# skv_v3.net
KiCad netlist of a schematic drawn in EAGLE
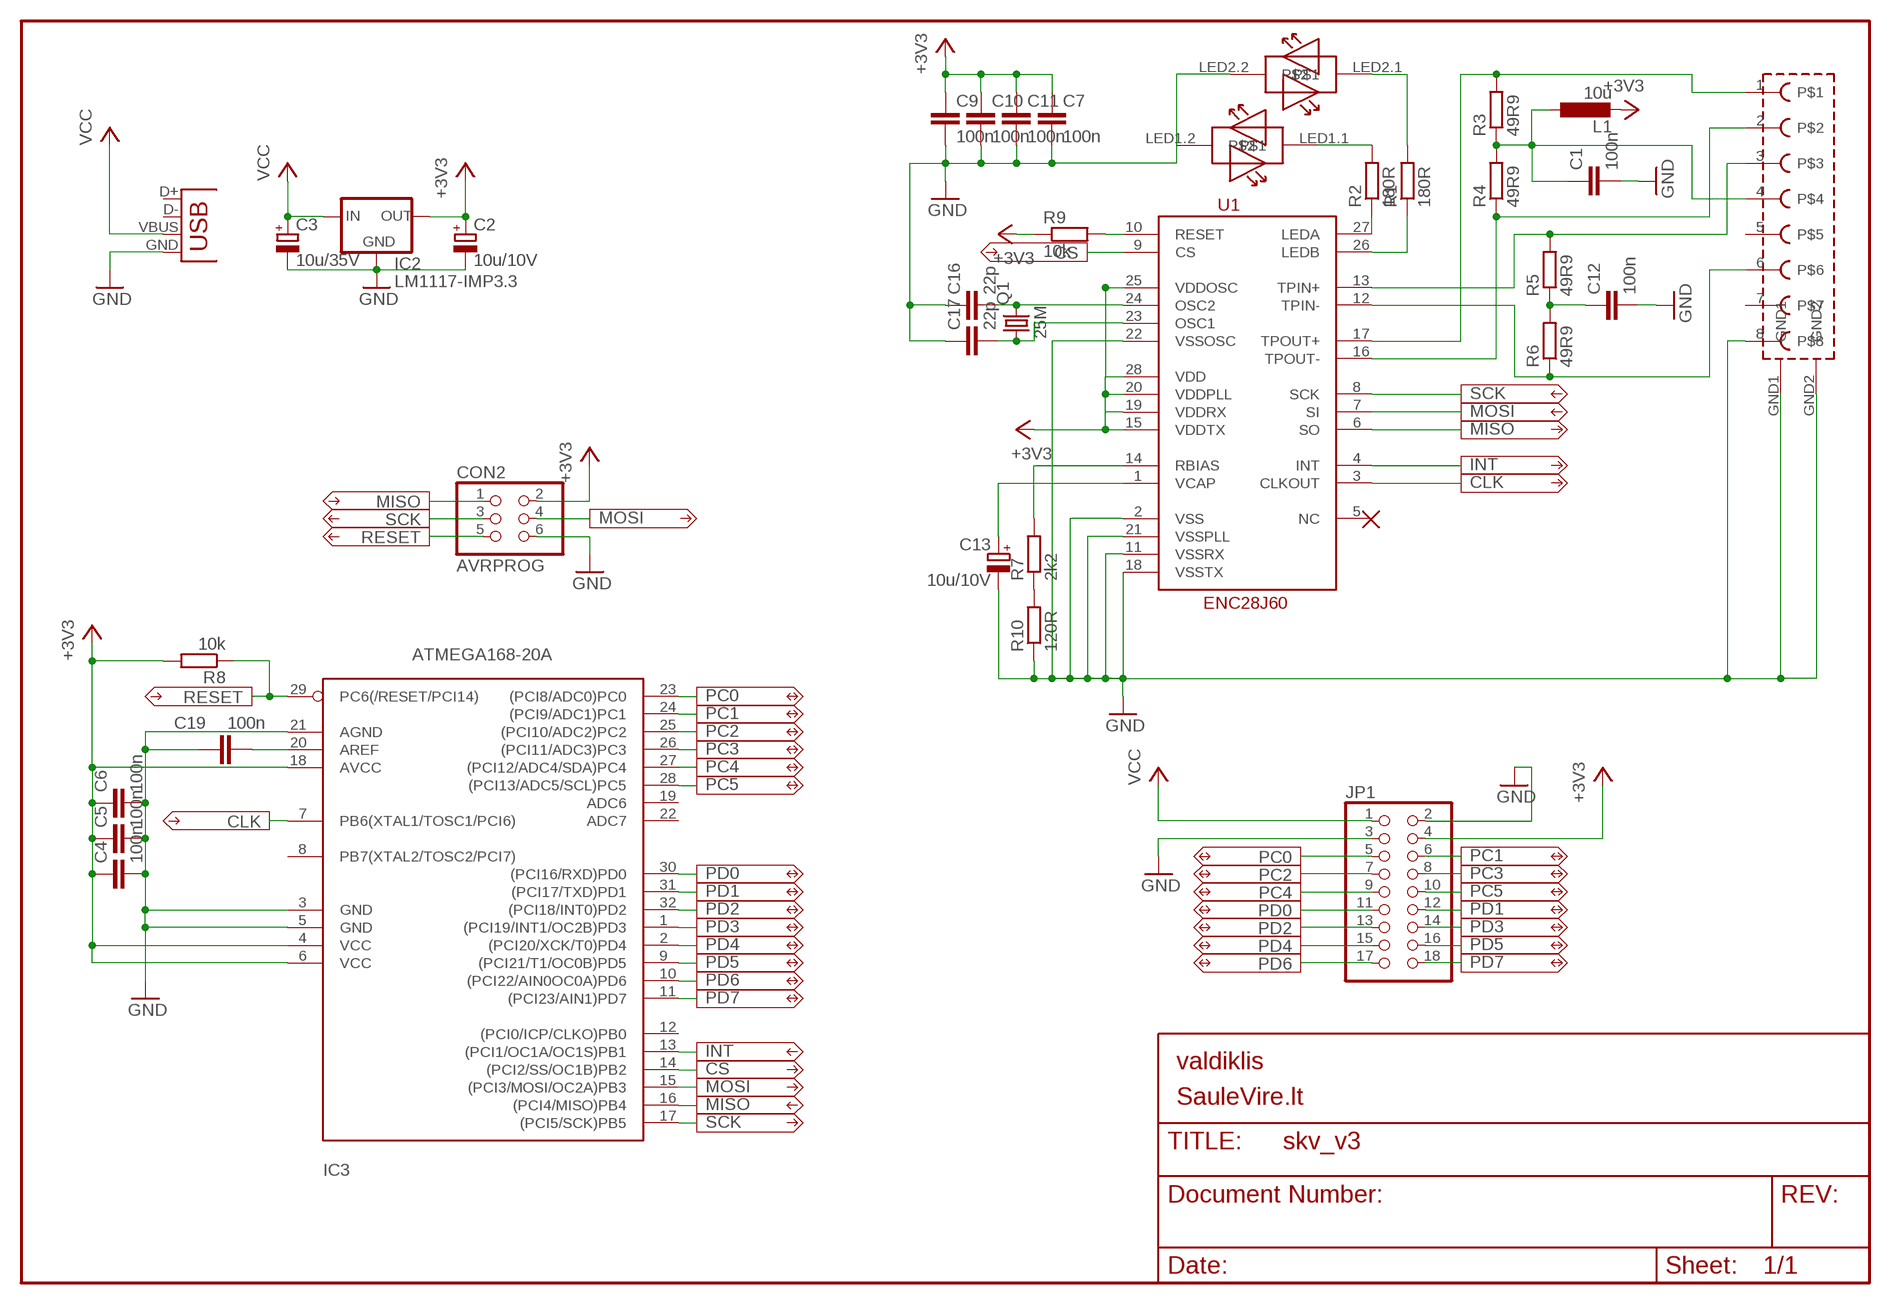
[diagram p0: schematic, sheet 1]

(export (version "E")
  (design (tool "Eeschema 10.0.6"))
  (components
    (comp (ref "C1")
      (value "100n")
      (footprint "eagle-import:C0805")
      (libsource (lib "eagle-import") (part "C-EUC0805"))
    )
    (comp (ref "C2")
      (value "10u/10V")
      (footprint "eagle-import:SMC_A")
      (libsource (lib "eagle-import") (part "CPOL-EUSMCA"))
    )
    (comp (ref "C3")
      (value "10u/35V")
      (footprint "eagle-import:SMC_C")
      (libsource (lib "eagle-import") (part "CPOL-EUSMCC"))
    )
    (comp (ref "C4")
      (value "100n")
      (footprint "eagle-import:C0805")
      (libsource (lib "eagle-import") (part "C-EUC0805"))
    )
    (comp (ref "C5")
      (value "100n")
      (footprint "eagle-import:C0805")
      (libsource (lib "eagle-import") (part "C-EUC0805"))
    )
    (comp (ref "C6")
      (value "100n")
      (footprint "eagle-import:C0805")
      (libsource (lib "eagle-import") (part "C-EUC0805"))
    )
    (comp (ref "C7")
      (value "100n")
      (footprint "eagle-import:C0805")
      (libsource (lib "eagle-import") (part "C-EUC0805"))
    )
    (comp (ref "C9")
      (value "100n")
      (footprint "eagle-import:C0805")
      (libsource (lib "eagle-import") (part "C-EUC0805"))
    )
    (comp (ref "C10")
      (value "100n")
      (footprint "eagle-import:C0805")
      (libsource (lib "eagle-import") (part "C-EUC0805"))
    )
    (comp (ref "C11")
      (value "100n")
      (footprint "eagle-import:C0805")
      (libsource (lib "eagle-import") (part "C-EUC0805"))
    )
    (comp (ref "C12")
      (value "100n")
      (footprint "eagle-import:C0805")
      (libsource (lib "eagle-import") (part "C-EUC0805"))
    )
    (comp (ref "C13")
      (value "10u/10V")
      (footprint "eagle-import:SMC_A")
      (libsource (lib "eagle-import") (part "CPOL-EUSMCA"))
    )
    (comp (ref "C16")
      (value "22p")
      (footprint "eagle-import:C0805")
      (libsource (lib "eagle-import") (part "C-EUC0805"))
    )
    (comp (ref "C17")
      (value "22p")
      (footprint "eagle-import:C0805")
      (libsource (lib "eagle-import") (part "C-EUC0805"))
    )
    (comp (ref "C19")
      (value "100n")
      (footprint "eagle-import:C0805")
      (libsource (lib "eagle-import") (part "C-EUC0805"))
    )
    (comp (ref "CON2")
      (value "AVRPROG")
      (footprint "eagle-import:2X03")
      (libsource (lib "eagle-import") (part "PINHD-2X3_2.54"))
    )
    (comp (ref "IC2")
      (value "LM1117-IMP3.3")
      (footprint "eagle-import:SOT223")
      (libsource (lib "eagle-import") (part "LM1117"))
    )
    (comp (ref "IC3")
      (value "ATMEGA168-20A")
      (footprint "eagle-import:TQFP32-08")
      (libsource (lib "eagle-import") (part "ATMEGA168A-20"))
    )
    (comp (ref "JP1")
      (value "PINHD-2X9")
      (footprint "eagle-import:2X09")
      (libsource (lib "eagle-import") (part "PINHD-2X9"))
    )
    (comp (ref "L1")
      (value "10u")
      (footprint "eagle-import:0207_10")
      (libsource (lib "eagle-import") (part "L-EU0207/10"))
    )
    (comp (ref "MAGJACK")
      (value "MAGJACK")
      (footprint "eagle-import:MAGJACK")
      (libsource (lib "eagle-import") (part "MAGJACK"))
    )
    (comp (ref "Q1")
      (value "25M")
      (footprint "eagle-import:HC49UP")
      (libsource (lib "eagle-import") (part "CRYSTALHC49UP"))
    )
    (comp (ref "R1")
      (value "180R")
      (footprint "eagle-import:R0805")
      (libsource (lib "eagle-import") (part "R-EU_R0805"))
    )
    (comp (ref "R2")
      (value "180R")
      (footprint "eagle-import:R0805")
      (libsource (lib "eagle-import") (part "R-EU_R0805"))
    )
    (comp (ref "R3")
      (value "49R9")
      (footprint "eagle-import:R0805")
      (libsource (lib "eagle-import") (part "R-EU_R0805"))
    )
    (comp (ref "R4")
      (value "49R9")
      (footprint "eagle-import:R0805")
      (libsource (lib "eagle-import") (part "R-EU_R0805"))
    )
    (comp (ref "R5")
      (value "49R9")
      (footprint "eagle-import:R0805")
      (libsource (lib "eagle-import") (part "R-EU_R0805"))
    )
    (comp (ref "R6")
      (value "49R9")
      (footprint "eagle-import:R0805")
      (libsource (lib "eagle-import") (part "R-EU_R0805"))
    )
    (comp (ref "R7")
      (value "2k2")
      (footprint "eagle-import:R0805")
      (libsource (lib "eagle-import") (part "R-EU_R0805"))
    )
    (comp (ref "R8")
      (value "10k")
      (footprint "eagle-import:R0805")
      (libsource (lib "eagle-import") (part "R-EU_R0805"))
    )
    (comp (ref "R9")
      (value "10k")
      (footprint "eagle-import:R0805")
      (libsource (lib "eagle-import") (part "R-EU_R0805"))
    )
    (comp (ref "R10")
      (value "120R")
      (footprint "eagle-import:R0805")
      (libsource (lib "eagle-import") (part "R-EU_R0805"))
    )
    (comp (ref "U1")
      (value "ENC28J60-1")
      (footprint "eagle-import:SSOP28")
      (libsource (lib "eagle-import") (part "ENC28J60-1"))
    )
    (comp (ref "X1")
      (value "USB-MICROB")
      (footprint "eagle-import:USB-MICROB")
      (libsource (lib "eagle-import") (part "USB-MICROB"))
    )
  )
  (nets
    (net (code "1") (name "+3V3") (class "Default")
      (node (ref "C10") (pin "1") (pinfunction "1_1") (pintype "passive"))
      (node (ref "C11") (pin "1") (pinfunction "1_1") (pintype "passive"))
      (node (ref "C2") (pin "+") (pinfunction "+_+") (pintype "passive"))
      (node (ref "C4") (pin "1") (pinfunction "1_1") (pintype "passive"))
      (node (ref "C5") (pin "1") (pinfunction "1_1") (pintype "passive"))
      (node (ref "C6") (pin "1") (pinfunction "1_1") (pintype "passive"))
      (node (ref "C7") (pin "1") (pinfunction "1_1") (pintype "passive"))
      (node (ref "C9") (pin "1") (pinfunction "1_1") (pintype "passive"))
      (node (ref "CON2") (pin "2") (pinfunction "2_2") (pintype "passive"))
      (node (ref "IC2") (pin "2") (pinfunction "OUT_2") (pintype "passive"))
      (node (ref "IC3") (pin "18") (pinfunction "AVCC_18") (pintype "bidirectional"))
      (node (ref "IC3") (pin "4") (pinfunction "VCC_4") (pintype "power_in"))
      (node (ref "IC3") (pin "6") (pinfunction "VCC_6") (pintype "power_in"))
      (node (ref "JP1") (pin "4") (pinfunction "4_4") (pintype "passive"))
      (node (ref "L1") (pin "2") (pinfunction "2_2") (pintype "passive"))
      (node (ref "R8") (pin "2") (pinfunction "2_2") (pintype "passive"))
      (node (ref "R9") (pin "1") (pinfunction "1_1") (pintype "passive"))
      (node (ref "U1") (pin "15") (pinfunction "VDDTX_15") (pintype "bidirectional"))
      (node (ref "U1") (pin "19") (pinfunction "VDDRX_19") (pintype "bidirectional"))
      (node (ref "U1") (pin "20") (pinfunction "VDDPLL_20") (pintype "bidirectional"))
      (node (ref "U1") (pin "25") (pinfunction "VDDOSC_25") (pintype "bidirectional"))
      (node (ref "U1") (pin "28") (pinfunction "VDD_28") (pintype "bidirectional"))
    )
    (net (code "2") (name "/CLK") (class "Default")
      (node (ref "IC3") (pin "7") (pinfunction "PB6(XTAL1/TOSC1/PCI6)_7") (pintype "bidirectional"))
      (node (ref "U1") (pin "3") (pinfunction "CLKOUT_3") (pintype "bidirectional"))
    )
    (net (code "3") (name "/CS") (class "Default")
      (node (ref "IC3") (pin "14") (pinfunction "(PCI2/SS/OC1B)PB2_14") (pintype "bidirectional"))
      (node (ref "U1") (pin "9") (pinfunction "CS_9") (pintype "bidirectional"))
    )
    (net (code "4") (name "/INT") (class "Default")
      (node (ref "IC3") (pin "13") (pinfunction "(PCI1/OC1A/OC1S)PB1_13") (pintype "bidirectional"))
      (node (ref "U1") (pin "4") (pinfunction "INT_4") (pintype "bidirectional"))
    )
    (net (code "5") (name "/MISO") (class "Default")
      (node (ref "CON2") (pin "1") (pinfunction "1_1") (pintype "passive"))
      (node (ref "IC3") (pin "16") (pinfunction "(PCI4/MISO)PB4_16") (pintype "bidirectional"))
      (node (ref "U1") (pin "6") (pinfunction "SO_6") (pintype "bidirectional"))
    )
    (net (code "6") (name "/MOSI") (class "Default")
      (node (ref "CON2") (pin "4") (pinfunction "4_4") (pintype "passive"))
      (node (ref "IC3") (pin "15") (pinfunction "(PCI3/MOSI/OC2A)PB3_15") (pintype "bidirectional"))
      (node (ref "U1") (pin "7") (pinfunction "SI_7") (pintype "bidirectional"))
    )
    (net (code "7") (name "/PC0") (class "Default")
      (node (ref "IC3") (pin "23") (pinfunction "(PCI8/ADC0)PC0_23") (pintype "bidirectional"))
      (node (ref "JP1") (pin "5") (pinfunction "5_5") (pintype "passive"))
    )
    (net (code "8") (name "/PC1") (class "Default")
      (node (ref "IC3") (pin "24") (pinfunction "(PCI9/ADC1)PC1_24") (pintype "bidirectional"))
      (node (ref "JP1") (pin "6") (pinfunction "6_6") (pintype "passive"))
    )
    (net (code "9") (name "/PC2") (class "Default")
      (node (ref "IC3") (pin "25") (pinfunction "(PCI10/ADC2)PC2_25") (pintype "bidirectional"))
      (node (ref "JP1") (pin "7") (pinfunction "7_7") (pintype "passive"))
    )
    (net (code "10") (name "/PC3") (class "Default")
      (node (ref "IC3") (pin "26") (pinfunction "(PCI11/ADC3)PC3_26") (pintype "bidirectional"))
      (node (ref "JP1") (pin "8") (pinfunction "8_8") (pintype "passive"))
    )
    (net (code "11") (name "/PC4") (class "Default")
      (node (ref "IC3") (pin "27") (pinfunction "(PCI12/ADC4/SDA)PC4_27") (pintype "bidirectional"))
      (node (ref "JP1") (pin "9") (pinfunction "9_9") (pintype "passive"))
    )
    (net (code "12") (name "/PC5") (class "Default")
      (node (ref "IC3") (pin "28") (pinfunction "(PCI13/ADC5/SCL)PC5_28") (pintype "bidirectional"))
      (node (ref "JP1") (pin "10") (pinfunction "10_10") (pintype "passive"))
    )
    (net (code "13") (name "/PD0") (class "Default")
      (node (ref "IC3") (pin "30") (pinfunction "(PCI16/RXD)PD0_30") (pintype "bidirectional"))
      (node (ref "JP1") (pin "11") (pinfunction "11_11") (pintype "passive"))
    )
    (net (code "14") (name "/PD1") (class "Default")
      (node (ref "IC3") (pin "31") (pinfunction "(PCI17/TXD)PD1_31") (pintype "bidirectional"))
      (node (ref "JP1") (pin "12") (pinfunction "12_12") (pintype "passive"))
    )
    (net (code "15") (name "/PD2") (class "Default")
      (node (ref "IC3") (pin "32") (pinfunction "(PCI18/INT0)PD2_32") (pintype "bidirectional"))
      (node (ref "JP1") (pin "13") (pinfunction "13_13") (pintype "passive"))
    )
    (net (code "16") (name "/PD3") (class "Default")
      (node (ref "IC3") (pin "1") (pinfunction "(PCI19/INT1/OC2B)PD3_1") (pintype "bidirectional"))
      (node (ref "JP1") (pin "14") (pinfunction "14_14") (pintype "passive"))
    )
    (net (code "17") (name "/PD4") (class "Default")
      (node (ref "IC3") (pin "2") (pinfunction "(PCI20/XCK/T0)PD4_2") (pintype "bidirectional"))
      (node (ref "JP1") (pin "15") (pinfunction "15_15") (pintype "passive"))
    )
    (net (code "18") (name "/PD5") (class "Default")
      (node (ref "IC3") (pin "9") (pinfunction "(PCI21/T1/OC0B)PD5_9") (pintype "bidirectional"))
      (node (ref "JP1") (pin "16") (pinfunction "16_16") (pintype "passive"))
    )
    (net (code "19") (name "/PD6") (class "Default")
      (node (ref "IC3") (pin "10") (pinfunction "(PCI22/AIN0OC0A)PD6_10") (pintype "bidirectional"))
      (node (ref "JP1") (pin "17") (pinfunction "17_17") (pintype "passive"))
    )
    (net (code "20") (name "/PD7") (class "Default")
      (node (ref "IC3") (pin "11") (pinfunction "(PCI23/AIN1)PD7_11") (pintype "bidirectional"))
      (node (ref "JP1") (pin "18") (pinfunction "18_18") (pintype "passive"))
    )
    (net (code "21") (name "/RESET") (class "Default")
      (node (ref "CON2") (pin "5") (pinfunction "5_5") (pintype "passive"))
      (node (ref "IC3") (pin "29") (pinfunction "PC6(/RESET/PCI14)_29") (pintype "bidirectional"))
      (node (ref "R8") (pin "1") (pinfunction "1_1") (pintype "passive"))
    )
    (net (code "22") (name "/SCK") (class "Default")
      (node (ref "CON2") (pin "3") (pinfunction "3_3") (pintype "passive"))
      (node (ref "IC3") (pin "17") (pinfunction "(PCI5/SCK)PB5_17") (pintype "bidirectional"))
      (node (ref "U1") (pin "8") (pinfunction "SCK_8") (pintype "bidirectional"))
    )
    (net (code "23") (name "GND") (class "Default")
      (node (ref "C1") (pin "2") (pinfunction "2_2") (pintype "passive"))
      (node (ref "C10") (pin "2") (pinfunction "2_2") (pintype "passive"))
      (node (ref "C11") (pin "2") (pinfunction "2_2") (pintype "passive"))
      (node (ref "C12") (pin "2") (pinfunction "2_2") (pintype "passive"))
      (node (ref "C13") (pin "-") (pinfunction "-_-") (pintype "passive"))
      (node (ref "C16") (pin "1") (pinfunction "1_1") (pintype "passive"))
      (node (ref "C17") (pin "1") (pinfunction "1_1") (pintype "passive"))
      (node (ref "C19") (pin "1") (pinfunction "1_1") (pintype "passive"))
      (node (ref "C2") (pin "-") (pinfunction "-_-") (pintype "passive"))
      (node (ref "C3") (pin "-") (pinfunction "-_-") (pintype "passive"))
      (node (ref "C4") (pin "2") (pinfunction "2_2") (pintype "passive"))
      (node (ref "C5") (pin "2") (pinfunction "2_2") (pintype "passive"))
      (node (ref "C6") (pin "2") (pinfunction "2_2") (pintype "passive"))
      (node (ref "C7") (pin "2") (pinfunction "2_2") (pintype "passive"))
      (node (ref "C9") (pin "2") (pinfunction "2_2") (pintype "passive"))
      (node (ref "CON2") (pin "6") (pinfunction "6_6") (pintype "passive"))
      (node (ref "IC2") (pin "1") (pinfunction "GND_1") (pintype "input"))
      (node (ref "IC3") (pin "21") (pinfunction "AGND_21") (pintype "bidirectional"))
      (node (ref "IC3") (pin "3") (pinfunction "GND_3") (pintype "power_in"))
      (node (ref "IC3") (pin "5") (pinfunction "GND_5") (pintype "power_in"))
      (node (ref "JP1") (pin "2") (pinfunction "2_2") (pintype "passive"))
      (node (ref "JP1") (pin "3") (pinfunction "3_3") (pintype "passive"))
      (node (ref "MAGJACK") (pin "8") (pinfunction "P$8_8") (pintype "passive"))
      (node (ref "MAGJACK") (pin "GND1") (pinfunction "GND1_GND1") (pintype "passive"))
      (node (ref "MAGJACK") (pin "GND2") (pinfunction "GND2_GND2") (pintype "passive"))
      (node (ref "MAGJACK") (pin "LED1.2") (pinfunction "P$2_LED1.2") (pintype "passive"))
      (node (ref "MAGJACK") (pin "LED2.2") (pinfunction "P$2_LED2.2") (pintype "passive"))
      (node (ref "R10") (pin "1") (pinfunction "1_1") (pintype "passive"))
      (node (ref "U1") (pin "11") (pinfunction "VSSRX_11") (pintype "bidirectional"))
      (node (ref "U1") (pin "18") (pinfunction "VSSTX_18") (pintype "bidirectional"))
      (node (ref "U1") (pin "2") (pinfunction "VSS_2") (pintype "bidirectional"))
      (node (ref "U1") (pin "21") (pinfunction "VSSPLL_21") (pintype "bidirectional"))
      (node (ref "U1") (pin "22") (pinfunction "VSSOSC_22") (pintype "bidirectional"))
      (node (ref "X1") (pin "GND") (pinfunction "GND_GND") (pintype "bidirectional"))
    )
    (net (code "24") (name "Net-(C12-Pad1)") (class "Default")
      (node (ref "C12") (pin "1") (pinfunction "1_1") (pintype "passive"))
      (node (ref "R5") (pin "1") (pinfunction "1_1") (pintype "passive"))
      (node (ref "R6") (pin "2") (pinfunction "2_2") (pintype "passive"))
    )
    (net (code "25") (name "Net-(IC3-AREF)") (class "Default")
      (node (ref "C19") (pin "2") (pinfunction "2_2") (pintype "passive"))
      (node (ref "IC3") (pin "20") (pinfunction "AREF_20") (pintype "bidirectional"))
    )
    (net (code "26") (name "Net-(MAGJACKA-P$1)") (class "Default")
      (node (ref "MAGJACK") (pin "1") (pinfunction "P$1_1") (pintype "passive"))
      (node (ref "R3") (pin "2") (pinfunction "2_2") (pintype "passive"))
      (node (ref "U1") (pin "17") (pinfunction "TPOUT+_17") (pintype "bidirectional"))
    )
    (net (code "27") (name "Net-(MAGJACKA-P$2)") (class "Default")
      (node (ref "MAGJACK") (pin "2") (pinfunction "P$2_2") (pintype "passive"))
      (node (ref "R4") (pin "1") (pinfunction "1_1") (pintype "passive"))
      (node (ref "U1") (pin "16") (pinfunction "TPOUT-_16") (pintype "bidirectional"))
    )
    (net (code "28") (name "Net-(MAGJACKA-P$3)") (class "Default")
      (node (ref "MAGJACK") (pin "3") (pinfunction "P$3_3") (pintype "passive"))
      (node (ref "R5") (pin "2") (pinfunction "2_2") (pintype "passive"))
      (node (ref "U1") (pin "13") (pinfunction "TPIN+_13") (pintype "bidirectional"))
    )
    (net (code "29") (name "Net-(MAGJACKA-P$4)") (class "Default")
      (node (ref "C1") (pin "1") (pinfunction "1_1") (pintype "passive"))
      (node (ref "L1") (pin "1") (pinfunction "1_1") (pintype "passive"))
      (node (ref "MAGJACK") (pin "4") (pinfunction "P$4_4") (pintype "passive"))
      (node (ref "R3") (pin "1") (pinfunction "1_1") (pintype "passive"))
      (node (ref "R4") (pin "2") (pinfunction "2_2") (pintype "passive"))
    )
    (net (code "30") (name "Net-(MAGJACKA-P$6)") (class "Default")
      (node (ref "MAGJACK") (pin "6") (pinfunction "P$6_6") (pintype "passive"))
      (node (ref "R6") (pin "1") (pinfunction "1_1") (pintype "passive"))
      (node (ref "U1") (pin "12") (pinfunction "TPIN-_12") (pintype "bidirectional"))
    )
    (net (code "31") (name "Net-(MAGJACKB-P$1)") (class "Default")
      (node (ref "MAGJACK") (pin "LED1.1") (pinfunction "P$1_LED1.1") (pintype "passive"))
      (node (ref "R2") (pin "2") (pinfunction "2_2") (pintype "passive"))
    )
    (net (code "32") (name "Net-(MAGJACKC-P$1)") (class "Default")
      (node (ref "MAGJACK") (pin "LED2.1") (pinfunction "P$1_LED2.1") (pintype "passive"))
      (node (ref "R1") (pin "2") (pinfunction "2_2") (pintype "passive"))
    )
    (net (code "33") (name "Net-(R10-Pad2)") (class "Default")
      (node (ref "R10") (pin "2") (pinfunction "2_2") (pintype "passive"))
      (node (ref "R7") (pin "1") (pinfunction "1_1") (pintype "passive"))
    )
    (net (code "34") (name "Net-(U1-LEDA)") (class "Default")
      (node (ref "R2") (pin "1") (pinfunction "1_1") (pintype "passive"))
      (node (ref "U1") (pin "27") (pinfunction "LEDA_27") (pintype "bidirectional"))
    )
    (net (code "35") (name "Net-(U1-LEDB)") (class "Default")
      (node (ref "R1") (pin "1") (pinfunction "1_1") (pintype "passive"))
      (node (ref "U1") (pin "26") (pinfunction "LEDB_26") (pintype "bidirectional"))
    )
    (net (code "36") (name "Net-(U1-OSC1)") (class "Default")
      (node (ref "C17") (pin "2") (pinfunction "2_2") (pintype "passive"))
      (node (ref "Q1") (pin "1") (pinfunction "1_1") (pintype "passive"))
      (node (ref "U1") (pin "23") (pinfunction "OSC1_23") (pintype "bidirectional"))
    )
    (net (code "37") (name "Net-(U1-OSC2)") (class "Default")
      (node (ref "C16") (pin "2") (pinfunction "2_2") (pintype "passive"))
      (node (ref "Q1") (pin "2") (pinfunction "2_2") (pintype "passive"))
      (node (ref "U1") (pin "24") (pinfunction "OSC2_24") (pintype "bidirectional"))
    )
    (net (code "38") (name "Net-(U1-RBIAS)") (class "Default")
      (node (ref "R7") (pin "2") (pinfunction "2_2") (pintype "passive"))
      (node (ref "U1") (pin "14") (pinfunction "RBIAS_14") (pintype "bidirectional"))
    )
    (net (code "39") (name "Net-(U1-RESET)") (class "Default")
      (node (ref "R9") (pin "2") (pinfunction "2_2") (pintype "passive"))
      (node (ref "U1") (pin "10") (pinfunction "RESET_10") (pintype "bidirectional"))
    )
    (net (code "40") (name "Net-(U1-VCAP)") (class "Default")
      (node (ref "C13") (pin "+") (pinfunction "+_+") (pintype "passive"))
      (node (ref "U1") (pin "1") (pinfunction "VCAP_1") (pintype "bidirectional"))
    )
    (net (code "41") (name "VCC") (class "Default")
      (node (ref "C3") (pin "+") (pinfunction "+_+") (pintype "passive"))
      (node (ref "IC2") (pin "3") (pinfunction "IN_3") (pintype "input"))
      (node (ref "JP1") (pin "1") (pinfunction "1_1") (pintype "passive"))
      (node (ref "X1") (pin "VBUS") (pinfunction "VBUS_VBUS") (pintype "bidirectional"))
    )
    (net (code "42") (name "unconnected-(IC3-(PCI0{slash}ICP{slash}CLKO)PB0-Pad12)") (class "Default")
      (node (ref "IC3") (pin "12") (pinfunction "(PCI0/ICP/CLKO)PB0_12") (pintype "bidirectional"))
    )
    (net (code "43") (name "unconnected-(IC3-ADC6-Pad19)") (class "Default")
      (node (ref "IC3") (pin "19") (pinfunction "ADC6_19") (pintype "bidirectional"))
    )
    (net (code "44") (name "unconnected-(IC3-ADC7-Pad22)") (class "Default")
      (node (ref "IC3") (pin "22") (pinfunction "ADC7_22") (pintype "bidirectional"))
    )
    (net (code "45") (name "unconnected-(IC3-PB7(XTAL2{slash}TOSC2{slash}PCI7)-Pad8)") (class "Default")
      (node (ref "IC3") (pin "8") (pinfunction "PB7(XTAL2/TOSC2/PCI7)_8") (pintype "bidirectional"))
    )
    (net (code "46") (name "unconnected-(MAGJACKA-P$5-Pad5)") (class "Default")
      (node (ref "MAGJACK") (pin "5") (pinfunction "P$5_5") (pintype "passive"))
    )
    (net (code "47") (name "unconnected-(MAGJACKA-P$7-Pad7)") (class "Default")
      (node (ref "MAGJACK") (pin "7") (pinfunction "P$7_7") (pintype "passive"))
    )
    (net (code "48") (name "unconnected-(U1-NC-Pad5)") (class "Default")
      (node (ref "U1") (pin "5") (pinfunction "NC_5") (pintype "bidirectional"))
    )
    (net (code "49") (name "unconnected-(X1-PadD+)") (class "Default")
      (node (ref "X1") (pin "D+") (pinfunction "D+_D+") (pintype "bidirectional"))
    )
    (net (code "50") (name "unconnected-(X1-PadD-)") (class "Default")
      (node (ref "X1") (pin "D-") (pinfunction "D-_D-") (pintype "bidirectional"))
    )
  )
)
